# PROC091F_AOP_PWR.net
KiCad netlist of a schematic drawn in Altium Designer
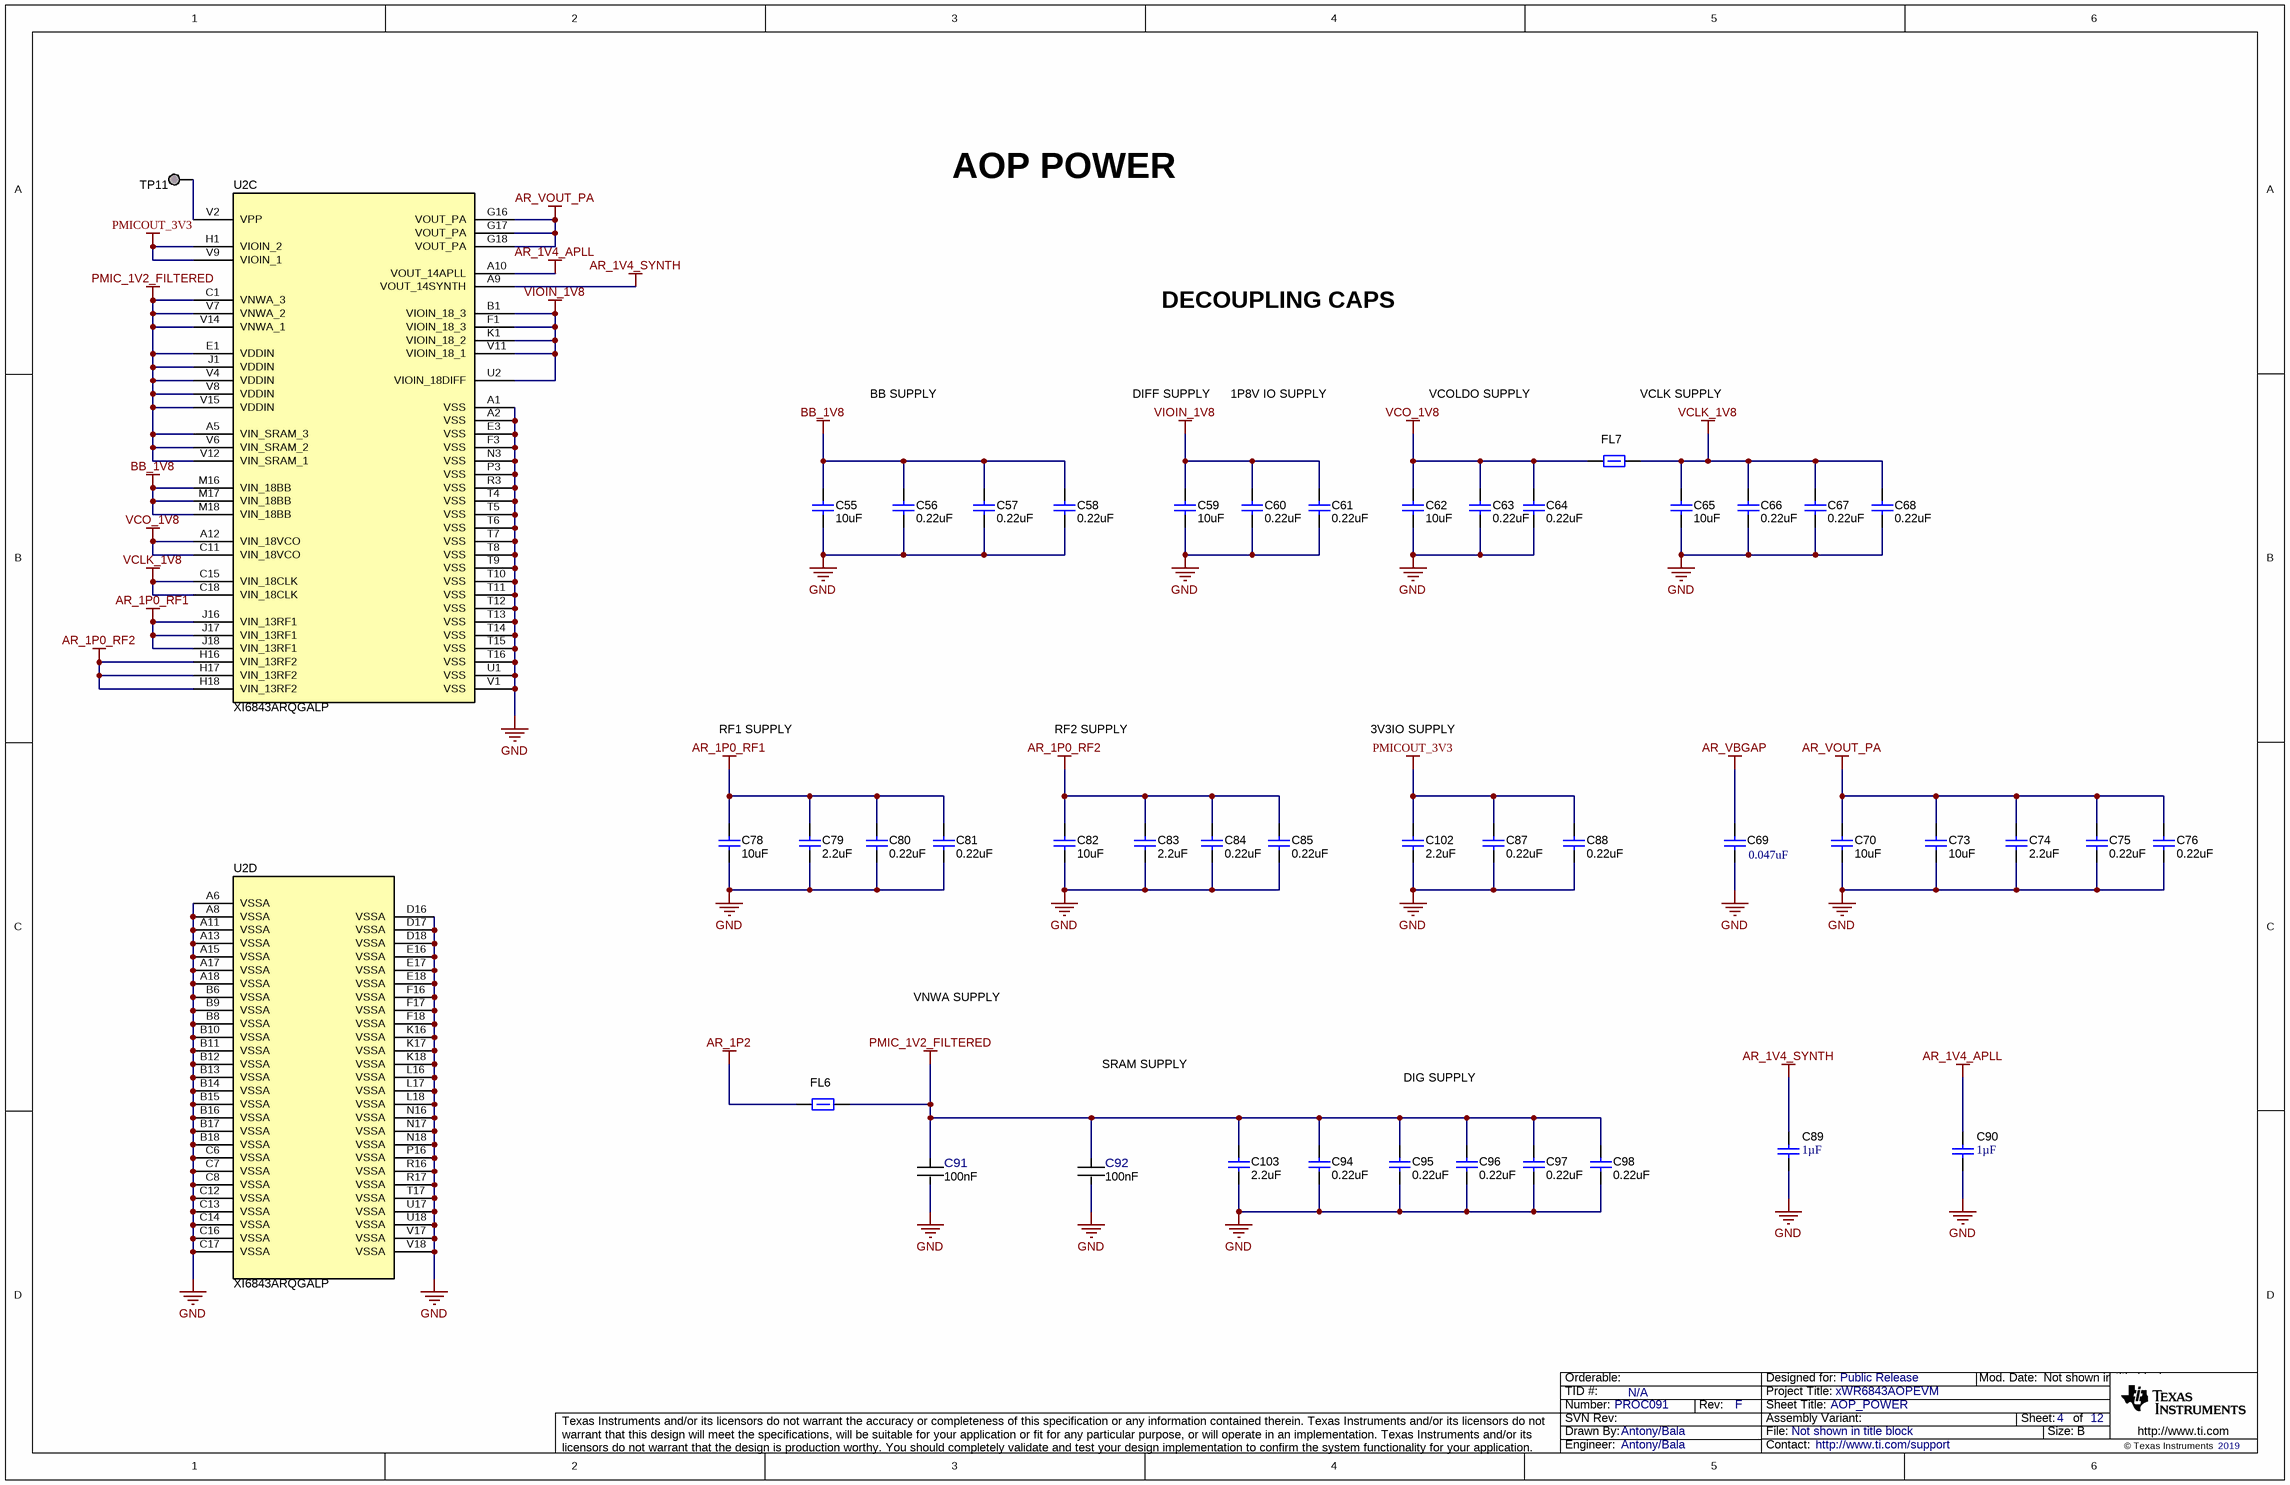
[diagram p0: PROC091F_AOP_PWR.SchDoc]

(export (version "E")
  (design (tool "Eeschema 10.0.6"))
  (components
    (comp (ref "C55")
      (value "10uF")
      (footprint "0402_070")
      (description "CAP, CERM, 10 uF, 10 V, +/- 20%, X5R, 0402")
      (fields
        (field (name "MANUFACTURER") "Samsung Electro-Mechanics")
        (field (name "PARTNUMBER") "CL05A106MP5NUNC")
      )
      (libsource (lib "Altium Vault - TI") (part "Capacitor"))
    )
    (comp (ref "C56")
      (value "0.22uF")
      (footprint "0201_033L")
      (description "CAP, CERM, 0.22 uF, 10 V, +/- 20%, X5R, 0201")
      (fields
        (field (name "MANUFACTURER") "Taiyo Yuden")
        (field (name "PARTNUMBER") "LMK063BJ224MP-F")
        (field (name "PUBLISHER") "Texas Instruments")
      )
      (libsource (lib "Altium Vault - TI") (part "Capacitor"))
    )
    (comp (ref "C57")
      (value "0.22uF")
      (footprint "0201_033L")
      (description "CAP, CERM, 0.22 uF, 10 V, +/- 20%, X5R, 0201")
      (fields
        (field (name "MANUFACTURER") "Taiyo Yuden")
        (field (name "PARTNUMBER") "LMK063BJ224MP-F")
        (field (name "PUBLISHER") "Texas Instruments")
      )
      (libsource (lib "Altium Vault - TI") (part "Capacitor"))
    )
    (comp (ref "C58")
      (value "0.22uF")
      (footprint "0201_033L")
      (description "CAP, CERM, 0.22 uF, 10 V, +/- 20%, X5R, 0201")
      (fields
        (field (name "MANUFACTURER") "Taiyo Yuden")
        (field (name "PARTNUMBER") "LMK063BJ224MP-F")
        (field (name "PUBLISHER") "Texas Instruments")
      )
      (libsource (lib "Altium Vault - TI") (part "Capacitor"))
    )
    (comp (ref "C59")
      (value "10uF")
      (footprint "0402_070")
      (description "CAP, CERM, 10 uF, 10 V, +/- 20%, X5R, 0402")
      (fields
        (field (name "MANUFACTURER") "Samsung Electro-Mechanics")
        (field (name "PARTNUMBER") "CL05A106MP5NUNC")
      )
      (libsource (lib "Altium Vault - TI") (part "Capacitor"))
    )
    (comp (ref "C60")
      (value "0.22uF")
      (footprint "0201_033L")
      (description "CAP, CERM, 0.22 uF, 10 V, +/- 20%, X5R, 0201")
      (fields
        (field (name "MANUFACTURER") "Taiyo Yuden")
        (field (name "PARTNUMBER") "LMK063BJ224MP-F")
        (field (name "PUBLISHER") "Texas Instruments")
      )
      (libsource (lib "Altium Vault - TI") (part "Capacitor"))
    )
    (comp (ref "C61")
      (value "0.22uF")
      (footprint "0201_033L")
      (description "CAP, CERM, 0.22 uF, 10 V, +/- 20%, X5R, 0201")
      (fields
        (field (name "MANUFACTURER") "Taiyo Yuden")
        (field (name "PARTNUMBER") "LMK063BJ224MP-F")
        (field (name "PUBLISHER") "Texas Instruments")
      )
      (libsource (lib "Altium Vault - TI") (part "Capacitor"))
    )
    (comp (ref "C62")
      (value "10uF")
      (footprint "0402_070")
      (description "CAP, CERM, 10 uF, 10 V, +/- 20%, X5R, 0402")
      (fields
        (field (name "MANUFACTURER") "Samsung Electro-Mechanics")
        (field (name "PARTNUMBER") "CL05A106MP5NUNC")
      )
      (libsource (lib "Altium Vault - TI") (part "Capacitor"))
    )
    (comp (ref "C63")
      (value "0.22uF")
      (footprint "0201_033L")
      (description "CAP, CERM, 0.22 uF, 10 V, +/- 20%, X5R, 0201")
      (fields
        (field (name "MANUFACTURER") "Taiyo Yuden")
        (field (name "PARTNUMBER") "LMK063BJ224MP-F")
        (field (name "PUBLISHER") "Texas Instruments")
      )
      (libsource (lib "Altium Vault - TI") (part "Capacitor"))
    )
    (comp (ref "C64")
      (value "0.22uF")
      (footprint "0201_033L")
      (description "CAP, CERM, 0.22 uF, 10 V, +/- 20%, X5R, 0201")
      (fields
        (field (name "MANUFACTURER") "Taiyo Yuden")
        (field (name "PARTNUMBER") "LMK063BJ224MP-F")
        (field (name "PUBLISHER") "Texas Instruments")
      )
      (libsource (lib "Altium Vault - TI") (part "Capacitor"))
    )
    (comp (ref "C65")
      (value "10uF")
      (footprint "0402_070")
      (description "CAP, CERM, 10 uF, 10 V, +/- 20%, X5R, 0402")
      (fields
        (field (name "MANUFACTURER") "Samsung Electro-Mechanics")
        (field (name "PARTNUMBER") "CL05A106MP5NUNC")
      )
      (libsource (lib "Altium Vault - TI") (part "Capacitor"))
    )
    (comp (ref "C66")
      (value "0.22uF")
      (footprint "0201_033L")
      (description "CAP, CERM, 0.22 uF, 10 V, +/- 20%, X5R, 0201")
      (fields
        (field (name "MANUFACTURER") "Taiyo Yuden")
        (field (name "PARTNUMBER") "LMK063BJ224MP-F")
        (field (name "PUBLISHER") "Texas Instruments")
      )
      (libsource (lib "Altium Vault - TI") (part "Capacitor"))
    )
    (comp (ref "C67")
      (value "0.22uF")
      (footprint "0201_033L")
      (description "CAP, CERM, 0.22 uF, 10 V, +/- 20%, X5R, 0201")
      (fields
        (field (name "MANUFACTURER") "Taiyo Yuden")
        (field (name "PARTNUMBER") "LMK063BJ224MP-F")
        (field (name "PUBLISHER") "Texas Instruments")
      )
      (libsource (lib "Altium Vault - TI") (part "Capacitor"))
    )
    (comp (ref "C68")
      (value "0.22uF")
      (footprint "0201_033L")
      (description "CAP, CERM, 0.22 uF, 10 V, +/- 20%, X5R, 0201")
      (fields
        (field (name "MANUFACTURER") "Taiyo Yuden")
        (field (name "PARTNUMBER") "LMK063BJ224MP-F")
        (field (name "PUBLISHER") "Texas Instruments")
      )
      (libsource (lib "Altium Vault - TI") (part "Capacitor"))
    )
    (comp (ref "C69")
      (value "GRM033R61C473KE84D")
      (footprint "0201_033L")
      (description "CAP, CERM, 0.047 uF, 16 V, +/- 10%, X5R, 0201")
      (fields
        (field (name "MANUFACTURER") "MuRata")
        (field (name "VALUEDISPLAYED") "0.047uF")
        (field (name "PUBLISHER") "Texas Instruments")
      )
      (libsource (lib "Altium Vault - TI") (part "Capacitor"))
    )
    (comp (ref "C70")
      (value "10uF")
      (footprint "0402_070")
      (description "CAP, CERM, 10 uF, 10 V, +/- 20%, X5R, 0402")
      (fields
        (field (name "MANUFACTURER") "Samsung Electro-Mechanics")
        (field (name "PARTNUMBER") "CL05A106MP5NUNC")
      )
      (libsource (lib "Altium Vault - TI") (part "Capacitor"))
    )
    (comp (ref "C73")
      (value "10uF")
      (footprint "0402_070")
      (description "CAP, CERM, 10 uF, 10 V, +/- 20%, X5R, 0402")
      (fields
        (field (name "MANUFACTURER") "Samsung Electro-Mechanics")
        (field (name "PARTNUMBER") "CL05A106MP5NUNC")
      )
      (libsource (lib "Altium Vault - TI") (part "Capacitor"))
    )
    (comp (ref "C74")
      (value "2.2uF")
      (footprint "0201L")
      (description "CAP, CERM, 2.2 uF, 6.3 V, +/- 20%, X5R, 0201")
      (fields
        (field (name "MANUFACTURER") "Samsung Electro-Mechanics")
        (field (name "PARTNUMBER") "CL03A225MQ3CRNC")
        (field (name "PUBLISHER") "Texas Instruments")
      )
      (libsource (lib "Altium Vault - TI") (part "Capacitor"))
    )
    (comp (ref "C75")
      (value "0.22uF")
      (footprint "0201_033L")
      (description "CAP, CERM, 0.22 uF, 10 V, +/- 20%, X5R, 0201")
      (fields
        (field (name "MANUFACTURER") "Taiyo Yuden")
        (field (name "PARTNUMBER") "LMK063BJ224MP-F")
        (field (name "PUBLISHER") "Texas Instruments")
      )
      (libsource (lib "Altium Vault - TI") (part "Capacitor"))
    )
    (comp (ref "C76")
      (value "0.22uF")
      (footprint "0201_033L")
      (description "CAP, CERM, 0.22 uF, 10 V, +/- 20%, X5R, 0201")
      (fields
        (field (name "MANUFACTURER") "Taiyo Yuden")
        (field (name "PARTNUMBER") "LMK063BJ224MP-F")
        (field (name "PUBLISHER") "Texas Instruments")
      )
      (libsource (lib "Altium Vault - TI") (part "Capacitor"))
    )
    (comp (ref "C78")
      (value "10uF")
      (footprint "0402_070")
      (description "CAP, CERM, 10 uF, 10 V, +/- 20%, X5R, 0402")
      (fields
        (field (name "MANUFACTURER") "Samsung Electro-Mechanics")
        (field (name "PARTNUMBER") "CL05A106MP5NUNC")
      )
      (libsource (lib "Altium Vault - TI") (part "Capacitor"))
    )
    (comp (ref "C79")
      (value "2.2uF")
      (footprint "0201L")
      (description "CAP, CERM, 2.2 uF, 6.3 V, +/- 20%, X5R, 0201")
      (fields
        (field (name "MANUFACTURER") "Samsung Electro-Mechanics")
        (field (name "PARTNUMBER") "CL03A225MQ3CRNC")
        (field (name "PUBLISHER") "Texas Instruments")
      )
      (libsource (lib "Altium Vault - TI") (part "Capacitor"))
    )
    (comp (ref "C80")
      (value "0.22uF")
      (footprint "0201_033L")
      (description "CAP, CERM, 0.22 uF, 10 V, +/- 20%, X5R, 0201")
      (fields
        (field (name "MANUFACTURER") "Taiyo Yuden")
        (field (name "PARTNUMBER") "LMK063BJ224MP-F")
        (field (name "PUBLISHER") "Texas Instruments")
      )
      (libsource (lib "Altium Vault - TI") (part "Capacitor"))
    )
    (comp (ref "C81")
      (value "0.22uF")
      (footprint "0201_033L")
      (description "CAP, CERM, 0.22 uF, 10 V, +/- 20%, X5R, 0201")
      (fields
        (field (name "MANUFACTURER") "Taiyo Yuden")
        (field (name "PARTNUMBER") "LMK063BJ224MP-F")
        (field (name "PUBLISHER") "Texas Instruments")
      )
      (libsource (lib "Altium Vault - TI") (part "Capacitor"))
    )
    (comp (ref "C82")
      (value "10uF")
      (footprint "0402_070")
      (description "CAP, CERM, 10 uF, 10 V, +/- 20%, X5R, 0402")
      (fields
        (field (name "MANUFACTURER") "Samsung Electro-Mechanics")
        (field (name "PARTNUMBER") "CL05A106MP5NUNC")
      )
      (libsource (lib "Altium Vault - TI") (part "Capacitor"))
    )
    (comp (ref "C83")
      (value "2.2uF")
      (footprint "0201L")
      (description "CAP, CERM, 2.2 uF, 6.3 V, +/- 20%, X5R, 0201")
      (fields
        (field (name "MANUFACTURER") "Samsung Electro-Mechanics")
        (field (name "PARTNUMBER") "CL03A225MQ3CRNC")
        (field (name "PUBLISHER") "Texas Instruments")
      )
      (libsource (lib "Altium Vault - TI") (part "Capacitor"))
    )
    (comp (ref "C84")
      (value "0.22uF")
      (footprint "0201_033L")
      (description "CAP, CERM, 0.22 uF, 10 V, +/- 20%, X5R, 0201")
      (fields
        (field (name "MANUFACTURER") "Taiyo Yuden")
        (field (name "PARTNUMBER") "LMK063BJ224MP-F")
        (field (name "PUBLISHER") "Texas Instruments")
      )
      (libsource (lib "Altium Vault - TI") (part "Capacitor"))
    )
    (comp (ref "C85")
      (value "0.22uF")
      (footprint "0201_033L")
      (description "CAP, CERM, 0.22 uF, 10 V, +/- 20%, X5R, 0201")
      (fields
        (field (name "MANUFACTURER") "Taiyo Yuden")
        (field (name "PARTNUMBER") "LMK063BJ224MP-F")
        (field (name "PUBLISHER") "Texas Instruments")
      )
      (libsource (lib "Altium Vault - TI") (part "Capacitor"))
    )
    (comp (ref "C87")
      (value "0.22uF")
      (footprint "0201_033L")
      (description "CAP, CERM, 0.22 uF, 10 V, +/- 20%, X5R, 0201")
      (fields
        (field (name "MANUFACTURER") "Taiyo Yuden")
        (field (name "PARTNUMBER") "LMK063BJ224MP-F")
        (field (name "PUBLISHER") "Texas Instruments")
      )
      (libsource (lib "Altium Vault - TI") (part "Capacitor"))
    )
    (comp (ref "C88")
      (value "0.22uF")
      (footprint "0201_033L")
      (description "CAP, CERM, 0.22 uF, 10 V, +/- 20%, X5R, 0201")
      (fields
        (field (name "MANUFACTURER") "Taiyo Yuden")
        (field (name "PARTNUMBER") "LMK063BJ224MP-F")
        (field (name "PUBLISHER") "Texas Instruments")
      )
      (libsource (lib "Altium Vault - TI") (part "Capacitor"))
    )
    (comp (ref "C89")
      (value "CGB2A1X6S0J105K033BC")
      (footprint "0402L")
      (description "CAP, CERM, 1 µF, 6.3 V,+/- 10%, X6S, 0402")
      (fields (field (name "MANUFACTURER") "TDK") (field (name "VALUEDISPLAYED") "1µF"))
      (libsource (lib "Altium Vault - TI") (part "CMP-0081763-1"))
    )
    (comp (ref "C90")
      (value "CGB2A1X6S0J105K033BC")
      (footprint "0402L")
      (description "CAP, CERM, 1 µF, 6.3 V,+/- 10%, X6S, 0402")
      (fields (field (name "MANUFACTURER") "TDK") (field (name "VALUEDISPLAYED") "1µF"))
      (libsource (lib "Altium Vault - TI") (part "CMP-0081763-1"))
    )
    (comp (ref "C91")
      (value "GRM033R6YA104KE14D")
      (footprint "FP-GRM033R6YA104KE14D_0201 (0603 Metric)-IPC_C")
      (description "Cap Ceramic 0.1uF 35V X5R 10% Pad SMD 0201 85C T/R")
      (fields (field (name "CAP_F") "100nF") (field (name "MANUFACTURER") "Murata Electronics North America"))
      (libsource (lib "Altium Vault - TI") (part "SYM-B32642B0223J"))
    )
    (comp (ref "C92")
      (value "GRM033R6YA104KE14D")
      (footprint "FP-GRM033R6YA104KE14D_0201 (0603 Metric)-IPC_C")
      (description "Cap Ceramic 0.1uF 35V X5R 10% Pad SMD 0201 85C T/R")
      (fields (field (name "CAP_F") "100nF") (field (name "MANUFACTURER") "Murata Electronics North America"))
      (libsource (lib "Altium Vault - TI") (part "SYM-B32642B0223J"))
    )
    (comp (ref "C94")
      (value "0.22uF")
      (footprint "0201_033L")
      (description "CAP, CERM, 0.22 uF, 10 V, +/- 20%, X5R, 0201")
      (fields
        (field (name "MANUFACTURER") "Taiyo Yuden")
        (field (name "PARTNUMBER") "LMK063BJ224MP-F")
        (field (name "PUBLISHER") "Texas Instruments")
      )
      (libsource (lib "Altium Vault - TI") (part "Capacitor"))
    )
    (comp (ref "C95")
      (value "0.22uF")
      (footprint "0201_033L")
      (description "CAP, CERM, 0.22 uF, 10 V, +/- 20%, X5R, 0201")
      (fields
        (field (name "MANUFACTURER") "Taiyo Yuden")
        (field (name "PARTNUMBER") "LMK063BJ224MP-F")
        (field (name "PUBLISHER") "Texas Instruments")
      )
      (libsource (lib "Altium Vault - TI") (part "Capacitor"))
    )
    (comp (ref "C96")
      (value "0.22uF")
      (footprint "0201_033L")
      (description "CAP, CERM, 0.22 uF, 10 V, +/- 20%, X5R, 0201")
      (fields
        (field (name "MANUFACTURER") "Taiyo Yuden")
        (field (name "PARTNUMBER") "LMK063BJ224MP-F")
        (field (name "PUBLISHER") "Texas Instruments")
      )
      (libsource (lib "Altium Vault - TI") (part "Capacitor"))
    )
    (comp (ref "C97")
      (value "0.22uF")
      (footprint "0201_033L")
      (description "CAP, CERM, 0.22 uF, 10 V, +/- 20%, X5R, 0201")
      (fields
        (field (name "MANUFACTURER") "Taiyo Yuden")
        (field (name "PARTNUMBER") "LMK063BJ224MP-F")
        (field (name "PUBLISHER") "Texas Instruments")
      )
      (libsource (lib "Altium Vault - TI") (part "Capacitor"))
    )
    (comp (ref "C98")
      (value "0.22uF")
      (footprint "0201_033L")
      (description "CAP, CERM, 0.22 uF, 10 V, +/- 20%, X5R, 0201")
      (fields
        (field (name "MANUFACTURER") "Taiyo Yuden")
        (field (name "PARTNUMBER") "LMK063BJ224MP-F")
        (field (name "PUBLISHER") "Texas Instruments")
      )
      (libsource (lib "Altium Vault - TI") (part "Capacitor"))
    )
    (comp (ref "C102")
      (value "2.2uF")
      (footprint "0201L")
      (description "CAP, CERM, 2.2 uF, 6.3 V, +/- 20%, X5R, 0201")
      (fields
        (field (name "MANUFACTURER") "Samsung Electro-Mechanics")
        (field (name "PARTNUMBER") "CL03A225MQ3CRNC")
        (field (name "PUBLISHER") "Texas Instruments")
      )
      (libsource (lib "Altium Vault - TI") (part "Capacitor"))
    )
    (comp (ref "C103")
      (value "2.2uF")
      (footprint "0201L")
      (description "CAP, CERM, 2.2 uF, 6.3 V, +/- 20%, X5R, 0201")
      (fields
        (field (name "MANUFACTURER") "Samsung Electro-Mechanics")
        (field (name "PARTNUMBER") "CL03A225MQ3CRNC")
        (field (name "PUBLISHER") "Texas Instruments")
      )
      (libsource (lib "Altium Vault - TI") (part "Capacitor"))
    )
    (comp (ref "FL6")
      (value "BLM15PD300SZ1D")
      (footprint "0402L")
      (description "Inductor, Ferrite Bead, Ferrite, 2.2 A, 0.035 ohm, AEC-Q200 Grade 1, SMD")
      (fields (field (name "MANUFACTURER") "MuRata") (field (name "PUBLISHER") "Texas Instruments"))
      (libsource (lib "Altium Vault - TI") (part "Ferrite_Bead"))
    )
    (comp (ref "FL7")
      (value "BLM15PD300SZ1D")
      (footprint "0402L")
      (description "Inductor, Ferrite Bead, Ferrite, 2.2 A, 0.035 ohm, AEC-Q200 Grade 1, SMD")
      (fields (field (name "MANUFACTURER") "MuRata") (field (name "PUBLISHER") "Texas Instruments"))
      (libsource (lib "Altium Vault - TI") (part "Ferrite_Bead"))
    )
    (comp (ref "TP11")
      (value "TESTPOINT")
      (footprint "TP_25MIL-SMT")
      (description "TEST POINT.  No entry in BOM.")
      (libsource (lib "Altium Vault - TI") (part "TESTPOINT"))
    )
    (comp (ref "U2")
      (value "XI6843ARQGALP")
      (footprint "ALP0180A")
      (description "XI6843ARQGALP, ALP0180A (BGA-180)")
      (fields (field (name "MANUFACTURER") "Texas Instruments") (field (name "PARTNUMBER") "XI6843ARQGALP"))
      (libsource (lib "Altium Vault - TI") (part "XI6843ARQGALP"))
    )
  )
  (nets
    (net (code "1") (name "AR_1P0_RF1") (class "Default")
      (node (ref "C78") (pin "1") (pinfunction "1_1") (pintype "passive"))
      (node (ref "C79") (pin "1") (pinfunction "1_1") (pintype "passive"))
      (node (ref "C80") (pin "1") (pinfunction "1_1") (pintype "passive"))
      (node (ref "C81") (pin "1") (pinfunction "1_1") (pintype "passive"))
      (node (ref "U2") (pin "J16") (pinfunction "VIN_13RF1_J16") (pintype "power_in"))
      (node (ref "U2") (pin "J17") (pinfunction "VIN_13RF1_J17") (pintype "power_in"))
      (node (ref "U2") (pin "J18") (pinfunction "VIN_13RF1_J18") (pintype "power_in"))
    )
    (net (code "2") (name "AR_1P0_RF2") (class "Default")
      (node (ref "C82") (pin "1") (pinfunction "1_1") (pintype "passive"))
      (node (ref "C83") (pin "1") (pinfunction "1_1") (pintype "passive"))
      (node (ref "C84") (pin "1") (pinfunction "1_1") (pintype "passive"))
      (node (ref "C85") (pin "1") (pinfunction "1_1") (pintype "passive"))
      (node (ref "U2") (pin "H16") (pinfunction "VIN_13RF2_H16") (pintype "power_in"))
      (node (ref "U2") (pin "H17") (pinfunction "VIN_13RF2_H17") (pintype "power_in"))
      (node (ref "U2") (pin "H18") (pinfunction "VIN_13RF2_H18") (pintype "power_in"))
    )
    (net (code "3") (name "AR_1P2") (class "Default")
      (node (ref "FL6") (pin "1") (pinfunction "1_1") (pintype "passive"))
    )
    (net (code "4") (name "AR_1V4_APLL") (class "Default")
      (node (ref "C90") (pin "1") (pinfunction "1_1") (pintype "passive"))
      (node (ref "U2") (pin "A10") (pinfunction "VOUT_14APLL_A10") (pintype "power_in"))
    )
    (net (code "5") (name "AR_1V4_SYNTH") (class "Default")
      (node (ref "C89") (pin "1") (pinfunction "1_1") (pintype "passive"))
      (node (ref "U2") (pin "A9") (pinfunction "VOUT_14SYNTH_A9") (pintype "power_in"))
    )
    (net (code "6") (name "AR_VBGAP") (class "Default")
      (node (ref "C69") (pin "1") (pinfunction "1_1") (pintype "passive"))
    )
    (net (code "7") (name "AR_VOUT_PA") (class "Default")
      (node (ref "C70") (pin "1") (pinfunction "1_1") (pintype "passive"))
      (node (ref "C73") (pin "1") (pinfunction "1_1") (pintype "passive"))
      (node (ref "C74") (pin "1") (pinfunction "1_1") (pintype "passive"))
      (node (ref "C75") (pin "1") (pinfunction "1_1") (pintype "passive"))
      (node (ref "C76") (pin "1") (pinfunction "1_1") (pintype "passive"))
      (node (ref "U2") (pin "G16") (pinfunction "VOUT_PA_G16") (pintype "power_in"))
      (node (ref "U2") (pin "G17") (pinfunction "VOUT_PA_G17") (pintype "power_in"))
      (node (ref "U2") (pin "G18") (pinfunction "VOUT_PA_G18") (pintype "power_in"))
    )
    (net (code "8") (name "BB_1V8") (class "Default")
      (node (ref "C55") (pin "1") (pinfunction "1_1") (pintype "passive"))
      (node (ref "C56") (pin "1") (pinfunction "1_1") (pintype "passive"))
      (node (ref "C57") (pin "1") (pinfunction "1_1") (pintype "passive"))
      (node (ref "C58") (pin "1") (pinfunction "1_1") (pintype "passive"))
      (node (ref "U2") (pin "M16") (pinfunction "VIN_18BB_M16") (pintype "power_in"))
      (node (ref "U2") (pin "M17") (pinfunction "VIN_18BB_M17") (pintype "power_in"))
      (node (ref "U2") (pin "M18") (pinfunction "VIN_18BB_M18") (pintype "power_in"))
    )
    (net (code "9") (name "GND") (class "Default")
      (node (ref "C102") (pin "2") (pinfunction "2_2") (pintype "passive"))
      (node (ref "C103") (pin "2") (pinfunction "2_2") (pintype "passive"))
      (node (ref "C55") (pin "2") (pinfunction "2_2") (pintype "passive"))
      (node (ref "C56") (pin "2") (pinfunction "2_2") (pintype "passive"))
      (node (ref "C57") (pin "2") (pinfunction "2_2") (pintype "passive"))
      (node (ref "C58") (pin "2") (pinfunction "2_2") (pintype "passive"))
      (node (ref "C59") (pin "2") (pinfunction "2_2") (pintype "passive"))
      (node (ref "C60") (pin "2") (pinfunction "2_2") (pintype "passive"))
      (node (ref "C61") (pin "2") (pinfunction "2_2") (pintype "passive"))
      (node (ref "C62") (pin "2") (pinfunction "2_2") (pintype "passive"))
      (node (ref "C63") (pin "2") (pinfunction "2_2") (pintype "passive"))
      (node (ref "C64") (pin "2") (pinfunction "2_2") (pintype "passive"))
      (node (ref "C65") (pin "2") (pinfunction "2_2") (pintype "passive"))
      (node (ref "C66") (pin "2") (pinfunction "2_2") (pintype "passive"))
      (node (ref "C67") (pin "2") (pinfunction "2_2") (pintype "passive"))
      (node (ref "C68") (pin "2") (pinfunction "2_2") (pintype "passive"))
      (node (ref "C69") (pin "2") (pinfunction "2_2") (pintype "passive"))
      (node (ref "C70") (pin "2") (pinfunction "2_2") (pintype "passive"))
      (node (ref "C73") (pin "2") (pinfunction "2_2") (pintype "passive"))
      (node (ref "C74") (pin "2") (pinfunction "2_2") (pintype "passive"))
      (node (ref "C75") (pin "2") (pinfunction "2_2") (pintype "passive"))
      (node (ref "C76") (pin "2") (pinfunction "2_2") (pintype "passive"))
      (node (ref "C78") (pin "2") (pinfunction "2_2") (pintype "passive"))
      (node (ref "C79") (pin "2") (pinfunction "2_2") (pintype "passive"))
      (node (ref "C80") (pin "2") (pinfunction "2_2") (pintype "passive"))
      (node (ref "C81") (pin "2") (pinfunction "2_2") (pintype "passive"))
      (node (ref "C82") (pin "2") (pinfunction "2_2") (pintype "passive"))
      (node (ref "C83") (pin "2") (pinfunction "2_2") (pintype "passive"))
      (node (ref "C84") (pin "2") (pinfunction "2_2") (pintype "passive"))
      (node (ref "C85") (pin "2") (pinfunction "2_2") (pintype "passive"))
      (node (ref "C87") (pin "2") (pinfunction "2_2") (pintype "passive"))
      (node (ref "C88") (pin "2") (pinfunction "2_2") (pintype "passive"))
      (node (ref "C89") (pin "2") (pinfunction "2_2") (pintype "passive"))
      (node (ref "C90") (pin "2") (pinfunction "2_2") (pintype "passive"))
      (node (ref "C91") (pin "2") (pinfunction "2_2") (pintype "passive"))
      (node (ref "C92") (pin "2") (pinfunction "2_2") (pintype "passive"))
      (node (ref "C94") (pin "2") (pinfunction "2_2") (pintype "passive"))
      (node (ref "C95") (pin "2") (pinfunction "2_2") (pintype "passive"))
      (node (ref "C96") (pin "2") (pinfunction "2_2") (pintype "passive"))
      (node (ref "C97") (pin "2") (pinfunction "2_2") (pintype "passive"))
      (node (ref "C98") (pin "2") (pinfunction "2_2") (pintype "passive"))
      (node (ref "U2") (pin "A1") (pinfunction "VSS_A1") (pintype "power_in"))
      (node (ref "U2") (pin "A11") (pinfunction "VSSA_A11") (pintype "power_in"))
      (node (ref "U2") (pin "A13") (pinfunction "VSSA_A13") (pintype "power_in"))
      (node (ref "U2") (pin "A15") (pinfunction "VSSA_A15") (pintype "power_in"))
      (node (ref "U2") (pin "A17") (pinfunction "VSSA_A17") (pintype "power_in"))
      (node (ref "U2") (pin "A18") (pinfunction "VSSA_A18") (pintype "power_in"))
      (node (ref "U2") (pin "A2") (pinfunction "VSS_A2") (pintype "power_in"))
      (node (ref "U2") (pin "A6") (pinfunction "VSSA_A6") (pintype "power_in"))
      (node (ref "U2") (pin "A8") (pinfunction "VSSA_A8") (pintype "power_in"))
      (node (ref "U2") (pin "B10") (pinfunction "VSSA_B10") (pintype "power_in"))
      (node (ref "U2") (pin "B11") (pinfunction "VSSA_B11") (pintype "power_in"))
      (node (ref "U2") (pin "B12") (pinfunction "VSSA_B12") (pintype "power_in"))
      (node (ref "U2") (pin "B13") (pinfunction "VSSA_B13") (pintype "power_in"))
      (node (ref "U2") (pin "B14") (pinfunction "VSSA_B14") (pintype "power_in"))
      (node (ref "U2") (pin "B15") (pinfunction "VSSA_B15") (pintype "power_in"))
      (node (ref "U2") (pin "B16") (pinfunction "VSSA_B16") (pintype "power_in"))
      (node (ref "U2") (pin "B17") (pinfunction "VSSA_B17") (pintype "power_in"))
      (node (ref "U2") (pin "B18") (pinfunction "VSSA_B18") (pintype "power_in"))
      (node (ref "U2") (pin "B6") (pinfunction "VSSA_B6") (pintype "power_in"))
      (node (ref "U2") (pin "B8") (pinfunction "VSSA_B8") (pintype "power_in"))
      (node (ref "U2") (pin "B9") (pinfunction "VSSA_B9") (pintype "power_in"))
      (node (ref "U2") (pin "C12") (pinfunction "VSSA_C12") (pintype "power_in"))
      (node (ref "U2") (pin "C13") (pinfunction "VSSA_C13") (pintype "power_in"))
      (node (ref "U2") (pin "C14") (pinfunction "VSSA_C14") (pintype "power_in"))
      (node (ref "U2") (pin "C16") (pinfunction "VSSA_C16") (pintype "power_in"))
      (node (ref "U2") (pin "C17") (pinfunction "VSSA_C17") (pintype "power_in"))
      (node (ref "U2") (pin "C6") (pinfunction "VSSA_C6") (pintype "power_in"))
      (node (ref "U2") (pin "C7") (pinfunction "VSSA_C7") (pintype "power_in"))
      (node (ref "U2") (pin "C8") (pinfunction "VSSA_C8") (pintype "power_in"))
      (node (ref "U2") (pin "D16") (pinfunction "VSSA_D16") (pintype "power_in"))
      (node (ref "U2") (pin "D17") (pinfunction "VSSA_D17") (pintype "power_in"))
      (node (ref "U2") (pin "D18") (pinfunction "VSSA_D18") (pintype "power_in"))
      (node (ref "U2") (pin "E16") (pinfunction "VSSA_E16") (pintype "power_in"))
      (node (ref "U2") (pin "E17") (pinfunction "VSSA_E17") (pintype "power_in"))
      (node (ref "U2") (pin "E18") (pinfunction "VSSA_E18") (pintype "power_in"))
      (node (ref "U2") (pin "E3") (pinfunction "VSS_E3") (pintype "power_in"))
      (node (ref "U2") (pin "F16") (pinfunction "VSSA_F16") (pintype "power_in"))
      (node (ref "U2") (pin "F17") (pinfunction "VSSA_F17") (pintype "power_in"))
      (node (ref "U2") (pin "F18") (pinfunction "VSSA_F18") (pintype "power_in"))
      (node (ref "U2") (pin "F3") (pinfunction "VSS_F3") (pintype "power_in"))
      (node (ref "U2") (pin "K16") (pinfunction "VSSA_K16") (pintype "power_in"))
      (node (ref "U2") (pin "K17") (pinfunction "VSSA_K17") (pintype "power_in"))
      (node (ref "U2") (pin "K18") (pinfunction "VSSA_K18") (pintype "power_in"))
      (node (ref "U2") (pin "L16") (pinfunction "VSSA_L16") (pintype "power_in"))
      (node (ref "U2") (pin "L17") (pinfunction "VSSA_L17") (pintype "power_in"))
      (node (ref "U2") (pin "L18") (pinfunction "VSSA_L18") (pintype "power_in"))
      (node (ref "U2") (pin "N16") (pinfunction "VSSA_N16") (pintype "power_in"))
      (node (ref "U2") (pin "N17") (pinfunction "VSSA_N17") (pintype "power_in"))
      (node (ref "U2") (pin "N18") (pinfunction "VSSA_N18") (pintype "power_in"))
      (node (ref "U2") (pin "N3") (pinfunction "VSS_N3") (pintype "power_in"))
      (node (ref "U2") (pin "P16") (pinfunction "VSSA_P16") (pintype "power_in"))
      (node (ref "U2") (pin "P3") (pinfunction "VSS_P3") (pintype "power_in"))
      (node (ref "U2") (pin "R16") (pinfunction "VSSA_R16") (pintype "power_in"))
      (node (ref "U2") (pin "R17") (pinfunction "VSSA_R17") (pintype "power_in"))
      (node (ref "U2") (pin "R3") (pinfunction "VSS_R3") (pintype "power_in"))
      (node (ref "U2") (pin "T10") (pinfunction "VSS_T10") (pintype "power_in"))
      (node (ref "U2") (pin "T11") (pinfunction "VSS_T11") (pintype "power_in"))
      (node (ref "U2") (pin "T12") (pinfunction "VSS_T12") (pintype "power_in"))
      (node (ref "U2") (pin "T13") (pinfunction "VSS_T13") (pintype "power_in"))
      (node (ref "U2") (pin "T14") (pinfunction "VSS_T14") (pintype "power_in"))
      (node (ref "U2") (pin "T15") (pinfunction "VSS_T15") (pintype "power_in"))
      (node (ref "U2") (pin "T16") (pinfunction "VSS_T16") (pintype "power_in"))
      (node (ref "U2") (pin "T17") (pinfunction "VSSA_T17") (pintype "power_in"))
      (node (ref "U2") (pin "T4") (pinfunction "VSS_T4") (pintype "power_in"))
      (node (ref "U2") (pin "T5") (pinfunction "VSS_T5") (pintype "power_in"))
      (node (ref "U2") (pin "T6") (pinfunction "VSS_T6") (pintype "power_in"))
      (node (ref "U2") (pin "T7") (pinfunction "VSS_T7") (pintype "power_in"))
      (node (ref "U2") (pin "T8") (pinfunction "VSS_T8") (pintype "power_in"))
      (node (ref "U2") (pin "T9") (pinfunction "VSS_T9") (pintype "power_in"))
      (node (ref "U2") (pin "U1") (pinfunction "VSS_U1") (pintype "power_in"))
      (node (ref "U2") (pin "U17") (pinfunction "VSSA_U17") (pintype "power_in"))
      (node (ref "U2") (pin "U18") (pinfunction "VSSA_U18") (pintype "power_in"))
      (node (ref "U2") (pin "V1") (pinfunction "VSS_V1") (pintype "power_in"))
      (node (ref "U2") (pin "V17") (pinfunction "VSSA_V17") (pintype "power_in"))
      (node (ref "U2") (pin "V18") (pinfunction "VSSA_V18") (pintype "power_in"))
    )
    (net (code "10") (name "Net-(U2C-VPP)") (class "Default")
      (node (ref "TP11") (pin "1") (pintype "passive"))
      (node (ref "U2") (pin "V2") (pinfunction "VPP_V2") (pintype "power_in"))
    )
    (net (code "11") (name "PMICOUT_3V3") (class "Default")
      (node (ref "C102") (pin "1") (pinfunction "1_1") (pintype "passive"))
      (node (ref "C87") (pin "1") (pinfunction "1_1") (pintype "passive"))
      (node (ref "C88") (pin "1") (pinfunction "1_1") (pintype "passive"))
      (node (ref "U2") (pin "H1") (pinfunction "VIOIN_2_H1") (pintype "power_in"))
      (node (ref "U2") (pin "V9") (pinfunction "VIOIN_1_V9") (pintype "power_in"))
    )
    (net (code "12") (name "PMIC_1V2_FILTERED") (class "Default")
      (node (ref "C103") (pin "1") (pinfunction "1_1") (pintype "passive"))
      (node (ref "C91") (pin "1") (pinfunction "1_1") (pintype "passive"))
      (node (ref "C92") (pin "1") (pinfunction "1_1") (pintype "passive"))
      (node (ref "C94") (pin "1") (pinfunction "1_1") (pintype "passive"))
      (node (ref "C95") (pin "1") (pinfunction "1_1") (pintype "passive"))
      (node (ref "C96") (pin "1") (pinfunction "1_1") (pintype "passive"))
      (node (ref "C97") (pin "1") (pinfunction "1_1") (pintype "passive"))
      (node (ref "C98") (pin "1") (pinfunction "1_1") (pintype "passive"))
      (node (ref "FL6") (pin "2") (pinfunction "2_2") (pintype "passive"))
      (node (ref "U2") (pin "A5") (pinfunction "VIN_SRAM_3_A5") (pintype "power_in"))
      (node (ref "U2") (pin "C1") (pinfunction "VNWA_3_C1") (pintype "power_in"))
      (node (ref "U2") (pin "E1") (pinfunction "VDDIN_E1") (pintype "power_in"))
      (node (ref "U2") (pin "J1") (pinfunction "VDDIN_J1") (pintype "power_in"))
      (node (ref "U2") (pin "V12") (pinfunction "VIN_SRAM_1_V12") (pintype "power_in"))
      (node (ref "U2") (pin "V14") (pinfunction "VNWA_1_V14") (pintype "power_in"))
      (node (ref "U2") (pin "V15") (pinfunction "VDDIN_V15") (pintype "power_in"))
      (node (ref "U2") (pin "V4") (pinfunction "VDDIN_V4") (pintype "power_in"))
      (node (ref "U2") (pin "V6") (pinfunction "VIN_SRAM_2_V6") (pintype "power_in"))
      (node (ref "U2") (pin "V7") (pinfunction "VNWA_2_V7") (pintype "power_in"))
      (node (ref "U2") (pin "V8") (pinfunction "VDDIN_V8") (pintype "power_in"))
    )
    (net (code "13") (name "VCLK_1V8") (class "Default")
      (node (ref "C65") (pin "1") (pinfunction "1_1") (pintype "passive"))
      (node (ref "C66") (pin "1") (pinfunction "1_1") (pintype "passive"))
      (node (ref "C67") (pin "1") (pinfunction "1_1") (pintype "passive"))
      (node (ref "C68") (pin "1") (pinfunction "1_1") (pintype "passive"))
      (node (ref "FL7") (pin "2") (pinfunction "2_2") (pintype "passive"))
      (node (ref "U2") (pin "C15") (pinfunction "VIN_18CLK_C15") (pintype "power_in"))
      (node (ref "U2") (pin "C18") (pinfunction "VIN_18CLK_C18") (pintype "power_in"))
    )
    (net (code "14") (name "VCO_1V8") (class "Default")
      (node (ref "C62") (pin "1") (pinfunction "1_1") (pintype "passive"))
      (node (ref "C63") (pin "1") (pinfunction "1_1") (pintype "passive"))
      (node (ref "C64") (pin "1") (pinfunction "1_1") (pintype "passive"))
      (node (ref "FL7") (pin "1") (pinfunction "1_1") (pintype "passive"))
      (node (ref "U2") (pin "A12") (pinfunction "VIN_18VCO_A12") (pintype "power_in"))
      (node (ref "U2") (pin "C11") (pinfunction "VIN_18VCO_C11") (pintype "power_in"))
    )
    (net (code "15") (name "VIOIN_1V8") (class "Default")
      (node (ref "C59") (pin "1") (pinfunction "1_1") (pintype "passive"))
      (node (ref "C60") (pin "1") (pinfunction "1_1") (pintype "passive"))
      (node (ref "C61") (pin "1") (pinfunction "1_1") (pintype "passive"))
      (node (ref "U2") (pin "B1") (pinfunction "VIOIN_18_3_B1") (pintype "power_in"))
      (node (ref "U2") (pin "F1") (pinfunction "VIOIN_18_3_F1") (pintype "power_in"))
      (node (ref "U2") (pin "K1") (pinfunction "VIOIN_18_2_K1") (pintype "power_in"))
      (node (ref "U2") (pin "U2") (pinfunction "VIOIN_18DIFF_U2") (pintype "power_in"))
      (node (ref "U2") (pin "V11") (pinfunction "VIOIN_18_1_V11") (pintype "power_in"))
    )
  )
)
